# SparkFun_Tri_Axis_Accel_Breakout-LIS331.net
KiCad netlist of a schematic drawn in EAGLE
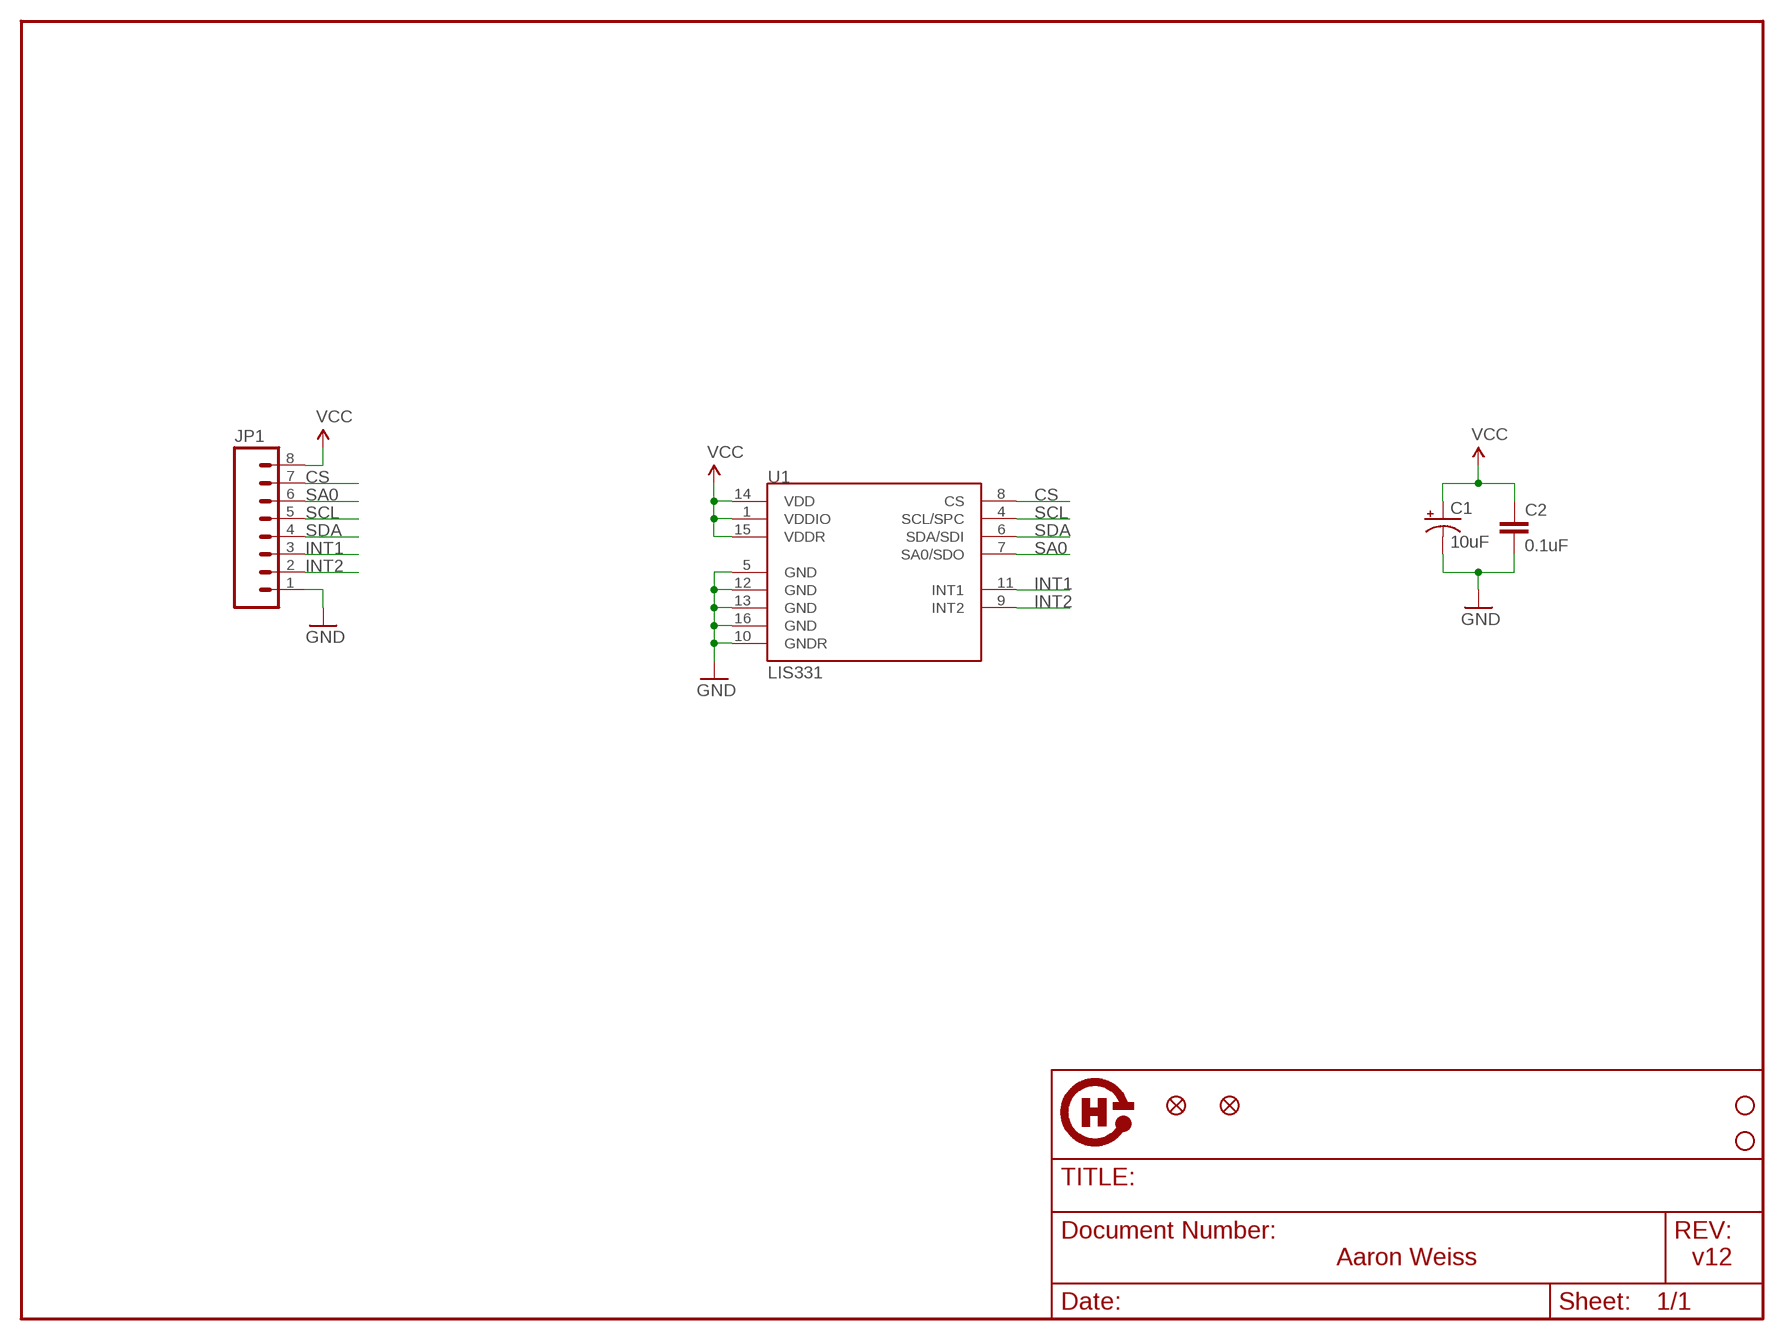
[diagram p0: schematic, sheet 1]

(export (version "E")
  (design (tool "Eeschema 10.0.6"))
  (components
    (comp (ref "C1")
      (value "10uF")
      (footprint "eagle-import:EIA3216")
      (libsource (lib "eagle-import") (part "CAP_POL1206"))
    )
    (comp (ref "C2")
      (value "0.1uF")
      (footprint "eagle-import:0402-CAP")
      (libsource (lib "eagle-import") (part "CAP0402-CAP"))
    )
    (comp (ref "JP1")
      (value "M08")
      (footprint "eagle-import:1X08")
      (libsource (lib "eagle-import") (part "M08"))
    )
    (comp (ref "JP3")
      (value "STAND-OFF")
      (footprint "eagle-import:STAND-OFF")
      (libsource (lib "eagle-import") (part "STAND-OFF"))
    )
    (comp (ref "JP4")
      (value "STAND-OFF")
      (footprint "eagle-import:STAND-OFF")
      (libsource (lib "eagle-import") (part "STAND-OFF"))
    )
    (comp (ref "JP5")
      (value "FIDUCIAL1X2")
      (footprint "eagle-import:FIDUCIAL-1X2")
      (libsource (lib "eagle-import") (part "FIDUCIAL1X2"))
    )
    (comp (ref "JP6")
      (value "FIDUCIAL1X2")
      (footprint "eagle-import:FIDUCIAL-1X2")
      (libsource (lib "eagle-import") (part "FIDUCIAL1X2"))
    )
    (comp (ref "U$1")
      (value "OSHW-LOGO-SMALL")
      (footprint "eagle-import:OSHW-LOGO-SMALL")
      (libsource (lib "eagle-import") (part "OSHW-LOGO-SMALL"))
    )
    (comp (ref "U1")
      (value "LIS331")
      (footprint "eagle-import:LGA16-3MM")
      (libsource (lib "eagle-import") (part "LIS331"))
    )
  )
  (nets
    (net (code "1") (name "/CS") (class "Default")
      (node (ref "JP1") (pin "7") (pinfunction "7_7") (pintype "passive"))
      (node (ref "U1") (pin "8") (pinfunction "CS_8") (pintype "bidirectional"))
    )
    (net (code "2") (name "/INT1") (class "Default")
      (node (ref "JP1") (pin "3") (pinfunction "3_3") (pintype "passive"))
      (node (ref "U1") (pin "11") (pinfunction "INT1_11") (pintype "bidirectional"))
    )
    (net (code "3") (name "/INT2") (class "Default")
      (node (ref "JP1") (pin "2") (pinfunction "2_2") (pintype "passive"))
      (node (ref "U1") (pin "9") (pinfunction "INT2_9") (pintype "bidirectional"))
    )
    (net (code "4") (name "/SA0") (class "Default")
      (node (ref "JP1") (pin "6") (pinfunction "6_6") (pintype "passive"))
      (node (ref "U1") (pin "7") (pinfunction "SA0/SDO_7") (pintype "bidirectional"))
    )
    (net (code "5") (name "/SCL") (class "Default")
      (node (ref "JP1") (pin "5") (pinfunction "5_5") (pintype "passive"))
      (node (ref "U1") (pin "4") (pinfunction "SCL/SPC_4") (pintype "bidirectional"))
    )
    (net (code "6") (name "/SDA") (class "Default")
      (node (ref "JP1") (pin "4") (pinfunction "4_4") (pintype "passive"))
      (node (ref "U1") (pin "6") (pinfunction "SDA/SDI_6") (pintype "bidirectional"))
    )
    (net (code "7") (name "GND") (class "Default")
      (node (ref "C1") (pin "C") (pinfunction "-_C") (pintype "passive"))
      (node (ref "C2") (pin "2") (pinfunction "2_2") (pintype "passive"))
      (node (ref "JP1") (pin "1") (pinfunction "1_1") (pintype "passive"))
      (node (ref "U1") (pin "10") (pinfunction "GNDR_10") (pintype "bidirectional"))
      (node (ref "U1") (pin "12") (pinfunction "GND_12") (pintype "bidirectional"))
      (node (ref "U1") (pin "13") (pinfunction "GND_13") (pintype "bidirectional"))
      (node (ref "U1") (pin "16") (pinfunction "GND_16") (pintype "bidirectional"))
      (node (ref "U1") (pin "5") (pinfunction "GND_5") (pintype "bidirectional"))
    )
    (net (code "8") (name "VCC") (class "Default")
      (node (ref "C1") (pin "A") (pinfunction "+_A") (pintype "passive"))
      (node (ref "C2") (pin "1") (pinfunction "1_1") (pintype "passive"))
      (node (ref "JP1") (pin "8") (pinfunction "8_8") (pintype "passive"))
      (node (ref "U1") (pin "1") (pinfunction "VDDIO_1") (pintype "bidirectional"))
      (node (ref "U1") (pin "14") (pinfunction "VDD_14") (pintype "bidirectional"))
      (node (ref "U1") (pin "15") (pinfunction "VDDR_15") (pintype "bidirectional"))
    )
  )
)
